# double_layer_relaycircuit.net
KiCad netlist of a schematic drawn in EAGLE
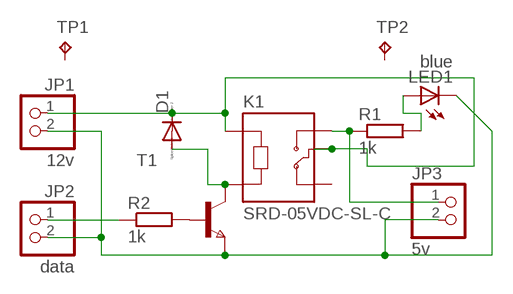
[diagram p0: schematic, sheet 1]

(export (version "E")
  (design (tool "Eeschema 10.0.6"))
  (components
    (comp (ref "D1")
      (value "DIODE-SOD323-W")
      (footprint "eagle-import:SOD323-W")
      (libsource (lib "eagle-import") (part "DIODE-SOD323-W"))
    )
    (comp (ref "JP1")
      (value "12v")
      (footprint "eagle-import:1X02")
      (libsource (lib "eagle-import") (part "PINHD-1X2"))
    )
    (comp (ref "JP2")
      (value "data")
      (footprint "eagle-import:1X02")
      (libsource (lib "eagle-import") (part "PINHD-1X2"))
    )
    (comp (ref "JP3")
      (value "5v")
      (footprint "eagle-import:1X02")
      (libsource (lib "eagle-import") (part "PINHD-1X2"))
    )
    (comp (ref "K1")
      (value "SRD-05VDC-SL-C")
      (footprint "eagle-import:RELAY_SRD-05VDC-SL-C")
      (fields (field (name "MF") "Songle Relay"))
      (libsource (lib "eagle-import") (part "SRD-05VDC-SL-C"))
    )
    (comp (ref "LED1")
      (value "blue")
      (footprint "eagle-import:LED5MM")
      (libsource (lib "eagle-import") (part "LED5MM"))
    )
    (comp (ref "R1")
      (value "1k")
      (footprint "eagle-import:M0805")
      (libsource (lib "eagle-import") (part "R-EU_M0805"))
    )
    (comp (ref "R2")
      (value "1k")
      (footprint "eagle-import:M0805")
      (libsource (lib "eagle-import") (part "R-EU_M0805"))
    )
    (comp (ref "T1")
      (value "NPNSOT23")
      (footprint "eagle-import:SOT-23")
      (fields (field (name "MPN") "DSS20201L-7"))
      (libsource (lib "eagle-import") (part "NPNSOT23"))
    )
    (comp (ref "TP1")
      (value "TPB1,27")
      (footprint "eagle-import:B1,27")
      (libsource (lib "eagle-import") (part "TPB1,27"))
    )
    (comp (ref "TP2")
      (value "TPB1,27")
      (footprint "eagle-import:B1,27")
      (libsource (lib "eagle-import") (part "TPB1,27"))
    )
  )
  (nets
    (net (code "1") (name "Net-(D1-PadC)") (class "Default")
      (node (ref "D1") (pin "C") (pinfunction "C_C") (pintype "passive"))
      (node (ref "JP1") (pin "1") (pinfunction "1_1") (pintype "passive"))
      (node (ref "K1") (pin "A1") (pinfunction "A1_A1") (pintype "passive"))
      (node (ref "K1") (pin "COM") (pinfunction "COM_COM") (pintype "passive"))
    )
    (net (code "2") (name "Net-(JP2-Pad1)") (class "Default")
      (node (ref "JP2") (pin "1") (pinfunction "1_1") (pintype "passive"))
      (node (ref "R2") (pin "1") (pinfunction "1_1") (pintype "passive"))
    )
    (net (code "3") (name "Net-(JP3-Pad1)") (class "Default")
      (node (ref "JP3") (pin "1") (pinfunction "1_1") (pintype "passive"))
      (node (ref "K1") (pin "NO") (pinfunction "NO_NO") (pintype "passive"))
      (node (ref "R1") (pin "1") (pinfunction "1_1") (pintype "passive"))
    )
    (net (code "4") (name "Net-(LED1-C)") (class "Default")
      (node (ref "JP1") (pin "2") (pinfunction "2_2") (pintype "passive"))
      (node (ref "JP2") (pin "2") (pinfunction "2_2") (pintype "passive"))
      (node (ref "JP3") (pin "2") (pinfunction "2_2") (pintype "passive"))
      (node (ref "LED1") (pin "K") (pinfunction "C_K") (pintype "passive"))
      (node (ref "T1") (pin "2") (pinfunction "E_2") (pintype "passive"))
    )
    (net (code "5") (name "Net-(LED1-PadA)") (class "Default")
      (node (ref "LED1") (pin "A") (pinfunction "A_A") (pintype "passive"))
      (node (ref "R1") (pin "2") (pinfunction "2_2") (pintype "passive"))
    )
    (net (code "6") (name "Net-(T1-B)") (class "Default")
      (node (ref "R2") (pin "2") (pinfunction "2_2") (pintype "passive"))
      (node (ref "T1") (pin "3") (pinfunction "B_3") (pintype "passive"))
    )
    (net (code "7") (name "Net-(T1-C)") (class "Default")
      (node (ref "D1") (pin "A") (pinfunction "A_A") (pintype "passive"))
      (node (ref "K1") (pin "A2") (pinfunction "A2_A2") (pintype "passive"))
      (node (ref "T1") (pin "1") (pinfunction "C_1") (pintype "passive"))
    )
    (net (code "8") (name "unconnected-(K1-PadNC)") (class "Default")
      (node (ref "K1") (pin "NC") (pinfunction "NC_NC") (pintype "passive"))
    )
    (net (code "9") (name "unconnected-(TP1-PadTP)") (class "Default")
      (node (ref "TP1") (pin "TP") (pinfunction "TP_TP") (pintype "input"))
    )
    (net (code "10") (name "unconnected-(TP2-PadTP)") (class "Default")
      (node (ref "TP2") (pin "TP") (pinfunction "TP_TP") (pintype "input"))
    )
  )
)
